# LED.net
KiCad netlist of a schematic drawn in Altium Designer
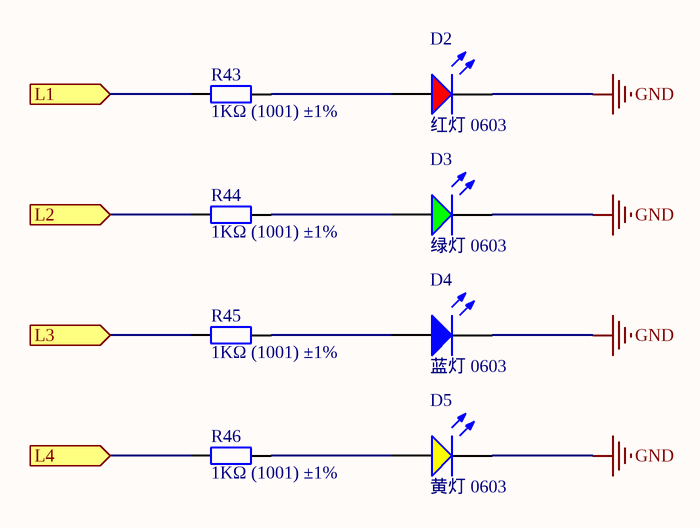
[diagram p0: LED.SchDoc]

(export (version "E")
  (design (tool "Eeschema 10.0.6"))
  (components
    (comp (ref "D2")
      (value "红灯 0603")
      (footprint "0603_LED_S1")
      (description "发光二极管")
      (libsource (lib "Miscellaneous Devices LC") (part "0603 红灯"))
    )
    (comp (ref "D3")
      (value "绿灯 0603")
      (footprint "0603_LED_S1")
      (description "发光二极管")
      (libsource (lib "Miscellaneous Devices LC") (part "0603 绿灯"))
    )
    (comp (ref "D4")
      (value "蓝灯 0603")
      (footprint "0603_LED_S1")
      (description "发光二极管")
      (libsource (lib "Miscellaneous Devices LC") (part "0603 蓝灯"))
    )
    (comp (ref "D5")
      (value "黄灯 0603")
      (footprint "0603_LED_S1")
      (description "发光二极管")
      (libsource (lib "Miscellaneous Devices LC") (part "0603 黄灯"))
    )
    (comp (ref "R43")
      (value "1KΩ (1001) ±1%")
      (footprint "0402_R")
      (description "贴片电阻")
      (libsource (lib "Miscellaneous Devices LC") (part "0402 1KΩ (1001) 1%"))
    )
    (comp (ref "R44")
      (value "1KΩ (1001) ±1%")
      (footprint "0402_R")
      (description "贴片电阻")
      (libsource (lib "Miscellaneous Devices LC") (part "0402 1KΩ (1001) 1%"))
    )
    (comp (ref "R45")
      (value "1KΩ (1001) ±1%")
      (footprint "0402_R")
      (description "贴片电阻")
      (libsource (lib "Miscellaneous Devices LC") (part "0402 1KΩ (1001) 1%"))
    )
    (comp (ref "R46")
      (value "1KΩ (1001) ±1%")
      (footprint "0402_R")
      (description "贴片电阻")
      (libsource (lib "Miscellaneous Devices LC") (part "0402 1KΩ (1001) 1%"))
    )
  )
  (nets
    (net (code "1") (name "/L1") (class "Default")
      (node (ref "R43") (pin "1") (pinfunction "1_1") (pintype "passive"))
    )
    (net (code "2") (name "/L2") (class "Default")
      (node (ref "R44") (pin "1") (pinfunction "1_1") (pintype "passive"))
    )
    (net (code "3") (name "/L3") (class "Default")
      (node (ref "R45") (pin "1") (pinfunction "1_1") (pintype "passive"))
    )
    (net (code "4") (name "/L4") (class "Default")
      (node (ref "R46") (pin "1") (pinfunction "1_1") (pintype "passive"))
    )
    (net (code "5") (name "GND") (class "Default")
      (node (ref "D2") (pin "K") (pinfunction "K_K") (pintype "passive"))
      (node (ref "D3") (pin "K") (pinfunction "K_K") (pintype "passive"))
      (node (ref "D4") (pin "K") (pinfunction "K_K") (pintype "passive"))
      (node (ref "D5") (pin "K") (pinfunction "K_K") (pintype "passive"))
    )
    (net (code "6") (name "Net-(D2-PadA)") (class "Default")
      (node (ref "D2") (pin "A") (pinfunction "A_A") (pintype "passive"))
      (node (ref "R43") (pin "2") (pinfunction "2_2") (pintype "passive"))
    )
    (net (code "7") (name "Net-(D3-PadA)") (class "Default")
      (node (ref "D3") (pin "A") (pinfunction "A_A") (pintype "passive"))
      (node (ref "R44") (pin "2") (pinfunction "2_2") (pintype "passive"))
    )
    (net (code "8") (name "Net-(D4-PadA)") (class "Default")
      (node (ref "D4") (pin "A") (pinfunction "A_A") (pintype "passive"))
      (node (ref "R45") (pin "2") (pinfunction "2_2") (pintype "passive"))
    )
    (net (code "9") (name "Net-(D5-PadA)") (class "Default")
      (node (ref "D5") (pin "A") (pinfunction "A_A") (pintype "passive"))
      (node (ref "R46") (pin "2") (pinfunction "2_2") (pintype "passive"))
    )
  )
)
